# VUE_PIC32_v1_0_Speed_Sensor.net
KiCad netlist of a schematic drawn in Altium Designer
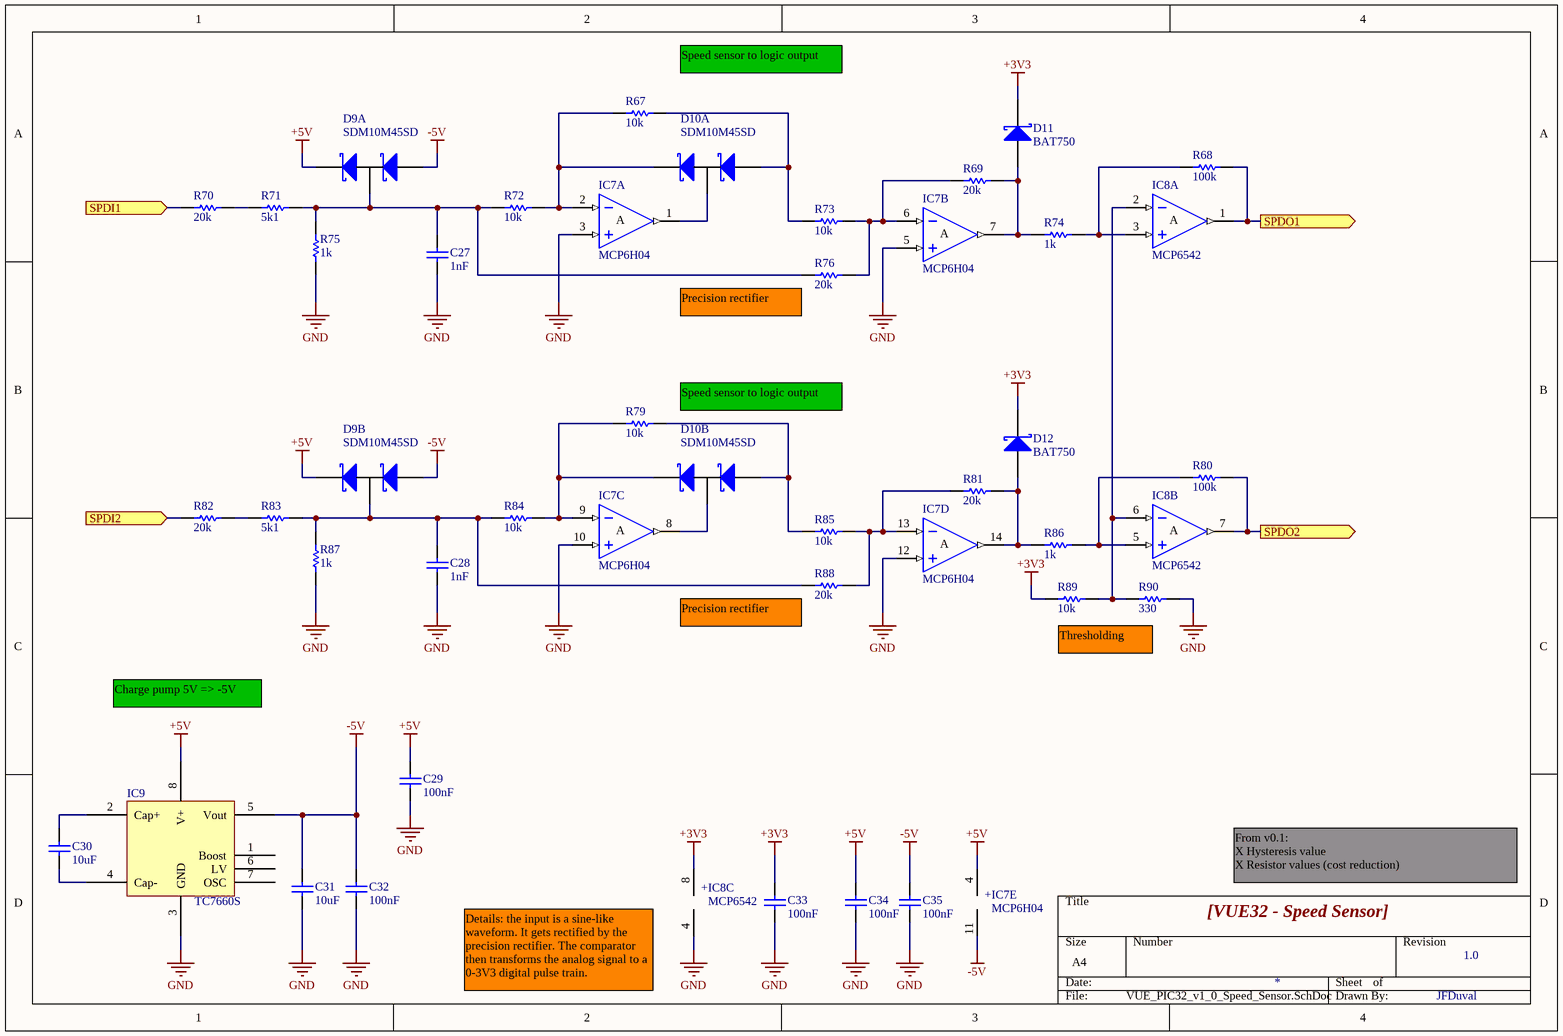
[diagram p0: VUE_PIC32_v1_0_Speed_Sensor.SchDoc]

(export (version "E")
  (design (tool "Eeschema 10.0.6"))
  (components
    (comp (ref "C27")
      (value "1nF")
      (footprint "0402C")
      (description "CAP CER 1000PF 25V 10% X7R 0402")
      (fields (field (name "MFG") "TDK") (field (name "MFGPARTNUMBER") "C1005X7R1E102K"))
      (libsource (lib "JFD_Cap") (part "CAP_TDK_C_0402_1nF_25V"))
    )
    (comp (ref "C28")
      (value "1nF")
      (footprint "0402C")
      (description "CAP CER 1000PF 25V 10% X7R 0402")
      (fields (field (name "MFG") "TDK") (field (name "MFGPARTNUMBER") "C1005X7R1E102K"))
      (libsource (lib "JFD_Cap") (part "CAP_TDK_C_0402_1nF_25V"))
    )
    (comp (ref "C29")
      (value "100nF")
      (footprint "0402C")
      (description "CAP CER 0.1UF 25V Y5V 0402")
      (fields (field (name "MFG") "TDK") (field (name "MFGPARTNUMBER") "C1005Y5V1E104Z"))
      (libsource (lib "JFD_Cap") (part "CAP_TDK_C_0402_100nF_25V"))
    )
    (comp (ref "C30")
      (value "10uF")
      (footprint "0805C")
      (description "CAP CER 10UF 16V Y5V 0805")
      (fields (field (name "MFG") "Murata") (field (name "MFGPARTNUMBER") "GRM21BF51C106ZE15L"))
      (libsource (lib "JFD_Cap") (part "CAP_MURATA_C_0805_10uF_16V"))
    )
    (comp (ref "C31")
      (value "10uF")
      (footprint "0805C")
      (description "CAP CER 10UF 16V Y5V 0805")
      (fields (field (name "MFG") "Murata") (field (name "MFGPARTNUMBER") "GRM21BF51C106ZE15L"))
      (libsource (lib "JFD_Cap") (part "CAP_MURATA_C_0805_10uF_16V"))
    )
    (comp (ref "C32")
      (value "100nF")
      (footprint "0402C")
      (description "CAP CER 0.1UF 25V Y5V 0402")
      (fields (field (name "MFG") "TDK") (field (name "MFGPARTNUMBER") "C1005Y5V1E104Z"))
      (libsource (lib "JFD_Cap") (part "CAP_TDK_C_0402_100nF_25V"))
    )
    (comp (ref "C33")
      (value "100nF")
      (footprint "0402C")
      (description "CAP CER 0.1UF 25V Y5V 0402")
      (fields (field (name "MFG") "TDK") (field (name "MFGPARTNUMBER") "C1005Y5V1E104Z"))
      (libsource (lib "JFD_Cap") (part "CAP_TDK_C_0402_100nF_25V"))
    )
    (comp (ref "C34")
      (value "100nF")
      (footprint "0402C")
      (description "CAP CER 0.1UF 25V Y5V 0402")
      (fields (field (name "MFG") "TDK") (field (name "MFGPARTNUMBER") "C1005Y5V1E104Z"))
      (libsource (lib "JFD_Cap") (part "CAP_TDK_C_0402_100nF_25V"))
    )
    (comp (ref "C35")
      (value "100nF")
      (footprint "0402C")
      (description "CAP CER 0.1UF 25V Y5V 0402")
      (fields (field (name "MFG") "TDK") (field (name "MFGPARTNUMBER") "C1005Y5V1E104Z"))
      (libsource (lib "JFD_Cap") (part "CAP_TDK_C_0402_100nF_25V"))
    )
    (comp (ref "D9")
      (value "SDM10M45SD")
      (footprint "SOT23-6")
      (description "DIODE SCHOTTKY ARRAY 45V SOT26")
      (fields (field (name "MFG") "Diodes Inc") (field (name "MFGPARTNUMBER") "SDM10M45SD-7-F"))
      (libsource (lib "JFD_Semi") (part "DIODE_DIODESINC_SDM10M45SD_QUAD_SCHOTTKY_45V_200MA"))
    )
    (comp (ref "D10")
      (value "SDM10M45SD")
      (footprint "SOT23-6")
      (description "DIODE SCHOTTKY ARRAY 45V SOT26")
      (fields (field (name "MFG") "Diodes Inc") (field (name "MFGPARTNUMBER") "SDM10M45SD-7-F"))
      (libsource (lib "JFD_Semi") (part "DIODE_DIODESINC_SDM10M45SD_QUAD_SCHOTTKY_45V_200MA"))
    )
    (comp (ref "D11")
      (value "BAT750")
      (footprint "SOT23-3")
      (description "DIODE SCHOTTKY 40V 750MA SOT23-3")
      (fields (field (name "MFG") "Diodes/Zetex") (field (name "MFGPARTNUMBER") "BAT750TA"))
      (libsource (lib "JFD_Semi") (part "DIODE_DIODESINC_BAT750_SCHOTTKY_SOT23_40V_750MA"))
    )
    (comp (ref "D12")
      (value "BAT750")
      (footprint "SOT23-3")
      (description "DIODE SCHOTTKY 40V 750MA SOT23-3")
      (fields (field (name "MFG") "Diodes/Zetex") (field (name "MFGPARTNUMBER") "BAT750TA"))
      (libsource (lib "JFD_Semi") (part "DIODE_DIODESINC_BAT750_SCHOTTKY_SOT23_40V_750MA"))
    )
    (comp (ref "IC7")
      (value "MCP6H04")
      (footprint "TSSOP14")
      (description "IC OPAMP QUAD16V 1.2MHZ 14TSSOP")
      (fields (field (name "MFG") "Microchip Technology") (field (name "MFGPARTNUMBER") "MCP6H04-E/ST"))
      (libsource (lib "JFD_IC") (part "IC_OPA_MICROCHIP_MCP6H04_QUAD_TSSOP14"))
    )
    (comp (ref "IC8")
      (value "MCP6542")
      (footprint "MSOP-8")
      (description "IC COMP 1.6V DUAL P-P 8SOIC")
      (fields (field (name "MFG") "Microchip Technology") (field (name "MFGPARTNUMBER") "MCP6542-E/MS"))
      (libsource (lib "JFD_IC") (part "IC_COMP_MICROCHIP_MCP6542_DUAL_MSOP8"))
    )
    (comp (ref "IC9")
      (value "TC7660S")
      (footprint "SOIC-8")
      (description "IC CHRG PUMP INV ADJ 20MA 8SOIC")
      (fields (field (name "MFG") "Microchip Technology") (field (name "MFGPARTNUMBER") "TC7660SEOA713"))
      (libsource (lib "JFD_IC") (part "IC_MICROCHIP_TC7660S_VOLT_INV_DBL_8SOIC"))
    )
    (comp (ref "R67")
      (value "10k")
      (footprint "0402")
      (description "RES 10.0K OHM 1/16W 1% 0402 SMD")
      (fields (field (name "MFG") "Yageo") (field (name "MFGPARTNUMBER") "RC0402FR-0710KL"))
      (libsource (lib "JFD_Res") (part "RES_YAGEO_0402_10K_1PCT"))
    )
    (comp (ref "R68")
      (value "100k")
      (footprint "0402")
      (description "RES 100K OHM 1/16W 1% 0402 SMD")
      (fields (field (name "MFG") "Yageo") (field (name "MFGPARTNUMBER") "RC0402FR-07100KL"))
      (libsource (lib "JFD_Res") (part "RES_YAGEO_0402_100K_1PCT"))
    )
    (comp (ref "R69")
      (value "20k")
      (footprint "0402")
      (description "RES 20.0K OHM 1/16W 1% 0402 SMD")
      (fields (field (name "MFG") "Yageo") (field (name "MFGPARTNUMBER") "RC0402FR-0720KL"))
      (libsource (lib "JFD_Res") (part "RES_YAGEO_0402_20K_1PCT"))
    )
    (comp (ref "R70")
      (value "20k")
      (footprint "0402")
      (description "RES 20.0K OHM 1/16W 1% 0402 SMD")
      (fields (field (name "MFG") "Yageo") (field (name "MFGPARTNUMBER") "RC0402FR-0720KL"))
      (libsource (lib "JFD_Res") (part "RES_YAGEO_0402_20K_1PCT"))
    )
    (comp (ref "R71")
      (value "5k1")
      (footprint "0402")
      (description "RES 5.10K OHM 1/16W 1% 0402 SMD")
      (fields (field (name "MFG") "Yageo") (field (name "MFGPARTNUMBER") "RC0402FR-075K1L"))
      (libsource (lib "JFD_Res") (part "RES_YAGEO_0402_5K1_1PCT"))
    )
    (comp (ref "R72")
      (value "10k")
      (footprint "0402")
      (description "RES 10.0K OHM 1/16W 1% 0402 SMD")
      (fields (field (name "MFG") "Yageo") (field (name "MFGPARTNUMBER") "RC0402FR-0710KL"))
      (libsource (lib "JFD_Res") (part "RES_YAGEO_0402_10K_1PCT"))
    )
    (comp (ref "R73")
      (value "10k")
      (footprint "0402")
      (description "RES 10.0K OHM 1/16W 1% 0402 SMD")
      (fields (field (name "MFG") "Yageo") (field (name "MFGPARTNUMBER") "RC0402FR-0710KL"))
      (libsource (lib "JFD_Res") (part "RES_YAGEO_0402_10K_1PCT"))
    )
    (comp (ref "R74")
      (value "1k")
      (footprint "0402")
      (description "RES 1.00K OHM 1/16W 1% 0402 SMD")
      (fields (field (name "MFG") "Yageo") (field (name "MFGPARTNUMBER") "RC0402FR-071KL"))
      (libsource (lib "JFD_Res") (part "RES_YAGEO_0402_1K_1PCT"))
    )
    (comp (ref "R75")
      (value "1k")
      (footprint "0402")
      (description "RES 1.00K OHM 1/16W 1% 0402 SMD")
      (fields (field (name "MFG") "Yageo") (field (name "MFGPARTNUMBER") "RC0402FR-071KL"))
      (libsource (lib "JFD_Res") (part "RES_YAGEO_0402_1K_1PCT"))
    )
    (comp (ref "R76")
      (value "20k")
      (footprint "0402")
      (description "RES 20.0K OHM 1/16W 1% 0402 SMD")
      (fields (field (name "MFG") "Yageo") (field (name "MFGPARTNUMBER") "RC0402FR-0720KL"))
      (libsource (lib "JFD_Res") (part "RES_YAGEO_0402_20K_1PCT"))
    )
    (comp (ref "R79")
      (value "10k")
      (footprint "0402")
      (description "RES 10.0K OHM 1/16W 1% 0402 SMD")
      (fields (field (name "MFG") "Yageo") (field (name "MFGPARTNUMBER") "RC0402FR-0710KL"))
      (libsource (lib "JFD_Res") (part "RES_YAGEO_0402_10K_1PCT"))
    )
    (comp (ref "R80")
      (value "100k")
      (footprint "0402")
      (description "RES 100K OHM 1/16W 1% 0402 SMD")
      (fields (field (name "MFG") "Yageo") (field (name "MFGPARTNUMBER") "RC0402FR-07100KL"))
      (libsource (lib "JFD_Res") (part "RES_YAGEO_0402_100K_1PCT"))
    )
    (comp (ref "R81")
      (value "20k")
      (footprint "0402")
      (description "RES 20.0K OHM 1/16W 1% 0402 SMD")
      (fields (field (name "MFG") "Yageo") (field (name "MFGPARTNUMBER") "RC0402FR-0720KL"))
      (libsource (lib "JFD_Res") (part "RES_YAGEO_0402_20K_1PCT"))
    )
    (comp (ref "R82")
      (value "20k")
      (footprint "0402")
      (description "RES 20.0K OHM 1/16W 1% 0402 SMD")
      (fields (field (name "MFG") "Yageo") (field (name "MFGPARTNUMBER") "RC0402FR-0720KL"))
      (libsource (lib "JFD_Res") (part "RES_YAGEO_0402_20K_1PCT"))
    )
    (comp (ref "R83")
      (value "5k1")
      (footprint "0402")
      (description "RES 5.10K OHM 1/16W 1% 0402 SMD")
      (fields (field (name "MFG") "Yageo") (field (name "MFGPARTNUMBER") "RC0402FR-075K1L"))
      (libsource (lib "JFD_Res") (part "RES_YAGEO_0402_5K1_1PCT"))
    )
    (comp (ref "R84")
      (value "10k")
      (footprint "0402")
      (description "RES 10.0K OHM 1/16W 1% 0402 SMD")
      (fields (field (name "MFG") "Yageo") (field (name "MFGPARTNUMBER") "RC0402FR-0710KL"))
      (libsource (lib "JFD_Res") (part "RES_YAGEO_0402_10K_1PCT"))
    )
    (comp (ref "R85")
      (value "10k")
      (footprint "0402")
      (description "RES 10.0K OHM 1/16W 1% 0402 SMD")
      (fields (field (name "MFG") "Yageo") (field (name "MFGPARTNUMBER") "RC0402FR-0710KL"))
      (libsource (lib "JFD_Res") (part "RES_YAGEO_0402_10K_1PCT"))
    )
    (comp (ref "R86")
      (value "1k")
      (footprint "0402")
      (description "RES 1.00K OHM 1/16W 1% 0402 SMD")
      (fields (field (name "MFG") "Yageo") (field (name "MFGPARTNUMBER") "RC0402FR-071KL"))
      (libsource (lib "JFD_Res") (part "RES_YAGEO_0402_1K_1PCT"))
    )
    (comp (ref "R87")
      (value "1k")
      (footprint "0402")
      (description "RES 1.00K OHM 1/16W 1% 0402 SMD")
      (fields (field (name "MFG") "Yageo") (field (name "MFGPARTNUMBER") "RC0402FR-071KL"))
      (libsource (lib "JFD_Res") (part "RES_YAGEO_0402_1K_1PCT"))
    )
    (comp (ref "R88")
      (value "20k")
      (footprint "0402")
      (description "RES 20.0K OHM 1/16W 1% 0402 SMD")
      (fields (field (name "MFG") "Yageo") (field (name "MFGPARTNUMBER") "RC0402FR-0720KL"))
      (libsource (lib "JFD_Res") (part "RES_YAGEO_0402_20K_1PCT"))
    )
    (comp (ref "R89")
      (value "10k")
      (footprint "0402")
      (description "RES 10.0K OHM 1/16W 1% 0402 SMD")
      (fields (field (name "MFG") "Yageo") (field (name "MFGPARTNUMBER") "RC0402FR-0710KL"))
      (libsource (lib "JFD_Res") (part "RES_YAGEO_0402_10K_1PCT"))
    )
    (comp (ref "R90")
      (value "330")
      (footprint "0402")
      (description "RES 330 OHM 1/16W 1% 0402 SMD")
      (fields (field (name "MFG") "Yageo") (field (name "MFGPARTNUMBER") "RC0402FR-07330RL"))
      (libsource (lib "JFD_Res") (part "RES_YAGEO_0402_330_1PCT"))
    )
  )
  (nets
    (net (code "1") (name "+3V3") (class "Default")
      (node (ref "C33") (pin "2") (pinfunction "2_2") (pintype "passive"))
      (node (ref "D11") (pin "3") (pinfunction "K_3") (pintype "passive"))
      (node (ref "D12") (pin "3") (pinfunction "K_3") (pintype "passive"))
      (node (ref "IC8") (pin "8") (pinfunction "VDD_8") (pintype "power_in"))
      (node (ref "R89") (pin "1") (pinfunction "1_1") (pintype "passive"))
    )
    (net (code "2") (name "+5V") (class "Default")
      (node (ref "C29") (pin "2") (pinfunction "2_2") (pintype "passive"))
      (node (ref "C34") (pin "2") (pinfunction "2_2") (pintype "passive"))
      (node (ref "D9") (pin "2") (pinfunction "K_2") (pintype "passive"))
      (node (ref "D9") (pin "5") (pinfunction "K_5") (pintype "passive"))
      (node (ref "IC7") (pin "4") (pinfunction "VDD_4") (pintype "power_in"))
      (node (ref "IC9") (pin "8") (pinfunction "V+_8") (pintype "power_in"))
    )
    (net (code "3") (name "-5V") (class "Default")
      (node (ref "C31") (pin "2") (pinfunction "2_2") (pintype "passive"))
      (node (ref "C32") (pin "2") (pinfunction "2_2") (pintype "passive"))
      (node (ref "C35") (pin "2") (pinfunction "2_2") (pintype "passive"))
      (node (ref "D9") (pin "1") (pinfunction "A_1") (pintype "passive"))
      (node (ref "D9") (pin "4") (pinfunction "A_4") (pintype "passive"))
      (node (ref "IC7") (pin "11") (pinfunction "VSS_11") (pintype "power_in"))
      (node (ref "IC9") (pin "5") (pinfunction "Vout_5") (pintype "passive"))
    )
    (net (code "4") (name "/SPDI1") (class "Default")
      (node (ref "R70") (pin "1") (pinfunction "1_1") (pintype "passive"))
    )
    (net (code "5") (name "/SPDI2") (class "Default")
      (node (ref "R82") (pin "1") (pinfunction "1_1") (pintype "passive"))
    )
    (net (code "6") (name "/SPDO1") (class "Default")
      (node (ref "IC8") (pin "1") (pinfunction "OUT_1") (pintype "output"))
      (node (ref "R68") (pin "2") (pinfunction "2_2") (pintype "passive"))
    )
    (net (code "7") (name "/SPDO2") (class "Default")
      (node (ref "IC8") (pin "7") (pinfunction "OUT_7") (pintype "output"))
      (node (ref "R80") (pin "2") (pinfunction "2_2") (pintype "passive"))
    )
    (net (code "8") (name "GND") (class "Default")
      (node (ref "C27") (pin "1") (pinfunction "1_1") (pintype "passive"))
      (node (ref "C28") (pin "1") (pinfunction "1_1") (pintype "passive"))
      (node (ref "C29") (pin "1") (pinfunction "1_1") (pintype "passive"))
      (node (ref "C31") (pin "1") (pinfunction "1_1") (pintype "passive"))
      (node (ref "C32") (pin "1") (pinfunction "1_1") (pintype "passive"))
      (node (ref "C33") (pin "1") (pinfunction "1_1") (pintype "passive"))
      (node (ref "C34") (pin "1") (pinfunction "1_1") (pintype "passive"))
      (node (ref "C35") (pin "1") (pinfunction "1_1") (pintype "passive"))
      (node (ref "IC7") (pin "10") (pinfunction "IN+_10") (pintype "input"))
      (node (ref "IC7") (pin "12") (pinfunction "IN+_12") (pintype "input"))
      (node (ref "IC7") (pin "3") (pinfunction "IN+_3") (pintype "input"))
      (node (ref "IC7") (pin "5") (pinfunction "IN+_5") (pintype "input"))
      (node (ref "IC8") (pin "4") (pinfunction "VSS_4") (pintype "power_in"))
      (node (ref "IC9") (pin "3") (pinfunction "GND_3") (pintype "power_in"))
      (node (ref "R75") (pin "1") (pinfunction "1_1") (pintype "passive"))
      (node (ref "R87") (pin "1") (pinfunction "1_1") (pintype "passive"))
      (node (ref "R90") (pin "2") (pinfunction "2_2") (pintype "passive"))
    )
    (net (code "9") (name "Net-(D9A-M)") (class "Default")
      (node (ref "C27") (pin "2") (pinfunction "2_2") (pintype "passive"))
      (node (ref "D9") (pin "6") (pinfunction "M_6") (pintype "passive"))
      (node (ref "R71") (pin "1") (pinfunction "1_1") (pintype "passive"))
      (node (ref "R72") (pin "1") (pinfunction "1_1") (pintype "passive"))
      (node (ref "R75") (pin "2") (pinfunction "2_2") (pintype "passive"))
      (node (ref "R76") (pin "1") (pinfunction "1_1") (pintype "passive"))
    )
    (net (code "10") (name "Net-(D9B-M)") (class "Default")
      (node (ref "C28") (pin "2") (pinfunction "2_2") (pintype "passive"))
      (node (ref "D9") (pin "3") (pinfunction "M_3") (pintype "passive"))
      (node (ref "R83") (pin "1") (pinfunction "1_1") (pintype "passive"))
      (node (ref "R84") (pin "1") (pinfunction "1_1") (pintype "passive"))
      (node (ref "R87") (pin "2") (pinfunction "2_2") (pintype "passive"))
      (node (ref "R88") (pin "1") (pinfunction "1_1") (pintype "passive"))
    )
    (net (code "11") (name "Net-(D10A-A)") (class "Default")
      (node (ref "D10") (pin "1") (pinfunction "A_1") (pintype "passive"))
      (node (ref "R67") (pin "2") (pinfunction "2_2") (pintype "passive"))
      (node (ref "R73") (pin "1") (pinfunction "1_1") (pintype "passive"))
    )
    (net (code "12") (name "Net-(D10A-K)") (class "Default")
      (node (ref "D10") (pin "2") (pinfunction "K_2") (pintype "passive"))
      (node (ref "IC7") (pin "2") (pinfunction "IN-_2") (pintype "input"))
      (node (ref "R67") (pin "1") (pinfunction "1_1") (pintype "passive"))
      (node (ref "R72") (pin "2") (pinfunction "2_2") (pintype "passive"))
    )
    (net (code "13") (name "Net-(D10A-M)") (class "Default")
      (node (ref "D10") (pin "6") (pinfunction "M_6") (pintype "passive"))
      (node (ref "IC7") (pin "1") (pinfunction "OUT_1") (pintype "output"))
    )
    (net (code "14") (name "Net-(D10B-A)") (class "Default")
      (node (ref "D10") (pin "4") (pinfunction "A_4") (pintype "passive"))
      (node (ref "R79") (pin "2") (pinfunction "2_2") (pintype "passive"))
      (node (ref "R85") (pin "1") (pinfunction "1_1") (pintype "passive"))
    )
    (net (code "15") (name "Net-(D10B-K)") (class "Default")
      (node (ref "D10") (pin "5") (pinfunction "K_5") (pintype "passive"))
      (node (ref "IC7") (pin "9") (pinfunction "IN-_9") (pintype "input"))
      (node (ref "R79") (pin "1") (pinfunction "1_1") (pintype "passive"))
      (node (ref "R84") (pin "2") (pinfunction "2_2") (pintype "passive"))
    )
    (net (code "16") (name "Net-(D10B-M)") (class "Default")
      (node (ref "D10") (pin "3") (pinfunction "M_3") (pintype "passive"))
      (node (ref "IC7") (pin "8") (pinfunction "OUT_8") (pintype "output"))
    )
    (net (code "17") (name "Net-(D11-A)") (class "Default")
      (node (ref "D11") (pin "1") (pinfunction "A_1") (pintype "passive"))
      (node (ref "IC7") (pin "7") (pinfunction "OUT_7") (pintype "output"))
      (node (ref "R69") (pin "2") (pinfunction "2_2") (pintype "passive"))
      (node (ref "R74") (pin "2") (pinfunction "2_2") (pintype "passive"))
    )
    (net (code "18") (name "Net-(D12-A)") (class "Default")
      (node (ref "D12") (pin "1") (pinfunction "A_1") (pintype "passive"))
      (node (ref "IC7") (pin "14") (pinfunction "OUT_14") (pintype "output"))
      (node (ref "R81") (pin "2") (pinfunction "2_2") (pintype "passive"))
      (node (ref "R86") (pin "2") (pinfunction "2_2") (pintype "passive"))
    )
    (net (code "19") (name "Net-(IC7B-IN-)") (class "Default")
      (node (ref "IC7") (pin "6") (pinfunction "IN-_6") (pintype "input"))
      (node (ref "R69") (pin "1") (pinfunction "1_1") (pintype "passive"))
      (node (ref "R73") (pin "2") (pinfunction "2_2") (pintype "passive"))
      (node (ref "R76") (pin "2") (pinfunction "2_2") (pintype "passive"))
    )
    (net (code "20") (name "Net-(IC7D-IN-)") (class "Default")
      (node (ref "IC7") (pin "13") (pinfunction "IN-_13") (pintype "input"))
      (node (ref "R81") (pin "1") (pinfunction "1_1") (pintype "passive"))
      (node (ref "R85") (pin "2") (pinfunction "2_2") (pintype "passive"))
      (node (ref "R88") (pin "2") (pinfunction "2_2") (pintype "passive"))
    )
    (net (code "21") (name "Net-(IC8A-IN+)") (class "Default")
      (node (ref "IC8") (pin "3") (pinfunction "IN+_3") (pintype "input"))
      (node (ref "R68") (pin "1") (pinfunction "1_1") (pintype "passive"))
      (node (ref "R74") (pin "1") (pinfunction "1_1") (pintype "passive"))
    )
    (net (code "22") (name "Net-(IC8A-IN-)") (class "Default")
      (node (ref "IC8") (pin "2") (pinfunction "IN-_2") (pintype "input"))
      (node (ref "IC8") (pin "6") (pinfunction "IN-_6") (pintype "input"))
      (node (ref "R89") (pin "2") (pinfunction "2_2") (pintype "passive"))
      (node (ref "R90") (pin "1") (pinfunction "1_1") (pintype "passive"))
    )
    (net (code "23") (name "Net-(IC8B-IN+)") (class "Default")
      (node (ref "IC8") (pin "5") (pinfunction "IN+_5") (pintype "input"))
      (node (ref "R80") (pin "1") (pinfunction "1_1") (pintype "passive"))
      (node (ref "R86") (pin "1") (pinfunction "1_1") (pintype "passive"))
    )
    (net (code "24") (name "Net-(IC9-Cap+)") (class "Default")
      (node (ref "C30") (pin "2") (pinfunction "2_2") (pintype "passive"))
      (node (ref "IC9") (pin "2") (pinfunction "Cap+_2") (pintype "passive"))
    )
    (net (code "25") (name "Net-(IC9-Cap-)") (class "Default")
      (node (ref "C30") (pin "1") (pinfunction "1_1") (pintype "passive"))
      (node (ref "IC9") (pin "4") (pinfunction "Cap-_4") (pintype "passive"))
    )
    (net (code "26") (name "Net-(R70-Pad2)") (class "Default")
      (node (ref "R70") (pin "2") (pinfunction "2_2") (pintype "passive"))
      (node (ref "R71") (pin "2") (pinfunction "2_2") (pintype "passive"))
    )
    (net (code "27") (name "Net-(R82-Pad2)") (class "Default")
      (node (ref "R82") (pin "2") (pinfunction "2_2") (pintype "passive"))
      (node (ref "R83") (pin "2") (pinfunction "2_2") (pintype "passive"))
    )
    (net (code "28") (name "unconnected-(IC9-Boost-Pad1)") (class "Default")
      (node (ref "IC9") (pin "1") (pinfunction "Boost_1") (pintype "passive"))
    )
    (net (code "29") (name "unconnected-(IC9-LV-Pad6)") (class "Default")
      (node (ref "IC9") (pin "6") (pinfunction "LV_6") (pintype "passive"))
    )
    (net (code "30") (name "unconnected-(IC9-OSC-Pad7)") (class "Default")
      (node (ref "IC9") (pin "7") (pinfunction "OSC_7") (pintype "passive"))
    )
  )
)
